# arduino_uno_to_attiny_x4.net
KiCad netlist of a schematic drawn in EAGLE
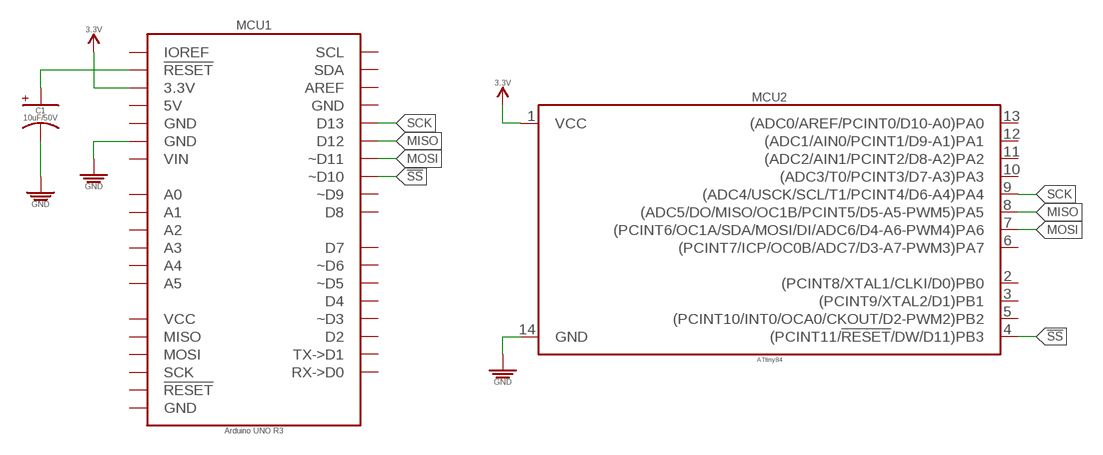
[diagram p0: schematic, sheet 1]

(export (version "E")
  (design (tool "Eeschema 10.0.6"))
  (components
    (comp (ref "C1")
      (value "10uF/50V")
      (footprint "eagle-import:_AE_PTH-DIA5-LS2-H5")
      (fields (field (name "MFR") "Panasonic Electronic Components") (field (name "MPN") "ECE-A1HKA100"))
      (libsource (lib "eagle-import") (part "10UF-POLARIZED_PTH_50V-20%"))
    )
    (comp (ref "MCU1")
      (value "Arduino UNO R3")
      (footprint "eagle-import:ARDUINO_UNO_R3")
      (fields (field (name "MFR") "Arduino") (field (name "MPN") "A000066"))
      (libsource (lib "eagle-import") (part "ARDUINO_UNO_R3"))
    )
    (comp (ref "MCU2")
      (value "ATtiny84")
      (footprint "eagle-import:DIP793W45P254L1919H533Q14B_DIP-14_ATTINY-X4")
      (fields (field (name "MFR") "Microchip Technology") (field (name "MPN") "ATTINY84A-PU"))
      (libsource (lib "eagle-import") (part "ATTINY-X4_DIP-14_ATTINY-84"))
    )
  )
  (nets
    (net (code "1") (name "/~{SS}") (class "Default")
      (node (ref "MCU1") (pin "D10") (pinfunction "~{D10}_D10") (pintype "bidirectional"))
      (node (ref "MCU2") (pin "4") (pinfunction "(PCINT11/~{RESET}/DW/D11)PB3_4") (pintype "bidirectional"))
    )
    (net (code "2") (name "3.3V") (class "Default")
      (node (ref "MCU1") (pin "3.3V") (pinfunction "3.3V_3.3V") (pintype "bidirectional"))
      (node (ref "MCU2") (pin "1") (pinfunction "VCC_1") (pintype "passive"))
    )
    (net (code "3") (name "GND") (class "Default")
      (node (ref "C1") (pin "-") (pinfunction "K_-") (pintype "passive"))
      (node (ref "MCU1") (pin "GND@3") (pinfunction "GND_GND@3") (pintype "bidirectional"))
      (node (ref "MCU2") (pin "14") (pinfunction "GND_14") (pintype "passive"))
    )
    (net (code "4") (name "MISO") (class "Default")
      (node (ref "MCU1") (pin "D12") (pinfunction "D12_D12") (pintype "bidirectional"))
      (node (ref "MCU2") (pin "8") (pinfunction "(ADC5/DO/MISO/OC1B/PCINT5/D5-A5-PWM5)PA5_8") (pintype "bidirectional"))
    )
    (net (code "5") (name "MOSI") (class "Default")
      (node (ref "MCU1") (pin "D11") (pinfunction "~{D11}_D11") (pintype "bidirectional"))
      (node (ref "MCU2") (pin "7") (pinfunction "(PCINT6/OC1A/SDA/MOSI/DI/ADC6/D4-A6-PWM4)PA6_7") (pintype "bidirectional"))
    )
    (net (code "6") (name "Net-(C1-A)") (class "Default")
      (node (ref "C1") (pin "+") (pinfunction "A_+") (pintype "passive"))
      (node (ref "MCU1") (pin "RESET@1") (pinfunction "~{RESET}_RESET@1") (pintype "bidirectional"))
    )
    (net (code "7") (name "SCK") (class "Default")
      (node (ref "MCU1") (pin "D13") (pinfunction "D13_D13") (pintype "bidirectional"))
      (node (ref "MCU2") (pin "9") (pinfunction "(ADC4/USCK/SCL/T1/PCINT4/D6-A4)PA4_9") (pintype "bidirectional"))
    )
    (net (code "8") (name "unconnected-(MCU1-GND-PadGND@1)") (class "Default")
      (node (ref "MCU1") (pin "GND@1") (pinfunction "GND_GND@1") (pintype "bidirectional"))
    )
    (net (code "9") (name "unconnected-(MCU1-GND-PadGND@2)") (class "Default")
      (node (ref "MCU1") (pin "GND@2") (pinfunction "GND_GND@2") (pintype "bidirectional"))
    )
    (net (code "10") (name "unconnected-(MCU1-GND-PadGND@4)") (class "Default")
      (node (ref "MCU1") (pin "GND@4") (pinfunction "GND_GND@4") (pintype "bidirectional"))
    )
    (net (code "11") (name "unconnected-(MCU1-Pad5V)") (class "Default")
      (node (ref "MCU1") (pin "5V") (pinfunction "5V_5V") (pintype "bidirectional"))
    )
    (net (code "12") (name "unconnected-(MCU1-PadA0)") (class "Default")
      (node (ref "MCU1") (pin "A0") (pinfunction "A0_A0") (pintype "bidirectional"))
    )
    (net (code "13") (name "unconnected-(MCU1-PadA1)") (class "Default")
      (node (ref "MCU1") (pin "A1") (pinfunction "A1_A1") (pintype "bidirectional"))
    )
    (net (code "14") (name "unconnected-(MCU1-PadA2)") (class "Default")
      (node (ref "MCU1") (pin "A2") (pinfunction "A2_A2") (pintype "bidirectional"))
    )
    (net (code "15") (name "unconnected-(MCU1-PadA3)") (class "Default")
      (node (ref "MCU1") (pin "A3") (pinfunction "A3_A3") (pintype "bidirectional"))
    )
    (net (code "16") (name "unconnected-(MCU1-PadA4)") (class "Default")
      (node (ref "MCU1") (pin "A4") (pinfunction "A4_A4") (pintype "bidirectional"))
    )
    (net (code "17") (name "unconnected-(MCU1-PadA5)") (class "Default")
      (node (ref "MCU1") (pin "A5") (pinfunction "A5_A5") (pintype "bidirectional"))
    )
    (net (code "18") (name "unconnected-(MCU1-PadAREF)") (class "Default")
      (node (ref "MCU1") (pin "AREF") (pinfunction "AREF_AREF") (pintype "bidirectional"))
    )
    (net (code "19") (name "unconnected-(MCU1-PadD2)") (class "Default")
      (node (ref "MCU1") (pin "D2") (pinfunction "D2_D2") (pintype "bidirectional"))
    )
    (net (code "20") (name "unconnected-(MCU1-PadD4)") (class "Default")
      (node (ref "MCU1") (pin "D4") (pinfunction "D4_D4") (pintype "bidirectional"))
    )
    (net (code "21") (name "unconnected-(MCU1-PadD7)") (class "Default")
      (node (ref "MCU1") (pin "D7") (pinfunction "D7_D7") (pintype "bidirectional"))
    )
    (net (code "22") (name "unconnected-(MCU1-PadD8)") (class "Default")
      (node (ref "MCU1") (pin "D8") (pinfunction "D8_D8") (pintype "bidirectional"))
    )
    (net (code "23") (name "unconnected-(MCU1-PadIOREF)") (class "Default")
      (node (ref "MCU1") (pin "IOREF") (pinfunction "IOREF_IOREF") (pintype "bidirectional"))
    )
    (net (code "24") (name "unconnected-(MCU1-PadMISO)") (class "Default")
      (node (ref "MCU1") (pin "MISO") (pinfunction "MISO_MISO") (pintype "bidirectional"))
    )
    (net (code "25") (name "unconnected-(MCU1-PadMOSI)") (class "Default")
      (node (ref "MCU1") (pin "MOSI") (pinfunction "MOSI_MOSI") (pintype "bidirectional"))
    )
    (net (code "26") (name "unconnected-(MCU1-PadSCK)") (class "Default")
      (node (ref "MCU1") (pin "SCK") (pinfunction "SCK_SCK") (pintype "bidirectional"))
    )
    (net (code "27") (name "unconnected-(MCU1-PadSCL)") (class "Default")
      (node (ref "MCU1") (pin "SCL") (pinfunction "SCL_SCL") (pintype "bidirectional"))
    )
    (net (code "28") (name "unconnected-(MCU1-PadSDA)") (class "Default")
      (node (ref "MCU1") (pin "SDA") (pinfunction "SDA_SDA") (pintype "bidirectional"))
    )
    (net (code "29") (name "unconnected-(MCU1-PadVCC)") (class "Default")
      (node (ref "MCU1") (pin "VCC") (pinfunction "VCC_VCC") (pintype "bidirectional"))
    )
    (net (code "30") (name "unconnected-(MCU1-PadVIN)") (class "Default")
      (node (ref "MCU1") (pin "VIN") (pinfunction "VIN_VIN") (pintype "bidirectional"))
    )
    (net (code "31") (name "unconnected-(MCU1-RX->D0-PadD0)") (class "Default")
      (node (ref "MCU1") (pin "D0") (pinfunction "RX->D0_D0") (pintype "bidirectional"))
    )
    (net (code "32") (name "unconnected-(MCU1-TX->D1-PadD1)") (class "Default")
      (node (ref "MCU1") (pin "D1") (pinfunction "TX->D1_D1") (pintype "bidirectional"))
    )
    (net (code "33") (name "unconnected-(MCU1-~{D3}-PadD3)") (class "Default")
      (node (ref "MCU1") (pin "D3") (pinfunction "~{D3}_D3") (pintype "bidirectional"))
    )
    (net (code "34") (name "unconnected-(MCU1-~{D5}-PadD5)") (class "Default")
      (node (ref "MCU1") (pin "D5") (pinfunction "~{D5}_D5") (pintype "bidirectional"))
    )
    (net (code "35") (name "unconnected-(MCU1-~{D6}-PadD6)") (class "Default")
      (node (ref "MCU1") (pin "D6") (pinfunction "~{D6}_D6") (pintype "bidirectional"))
    )
    (net (code "36") (name "unconnected-(MCU1-~{D9}-PadD9)") (class "Default")
      (node (ref "MCU1") (pin "D9") (pinfunction "~{D9}_D9") (pintype "bidirectional"))
    )
    (net (code "37") (name "unconnected-(MCU1-~{RESET}-PadRESET@2)") (class "Default")
      (node (ref "MCU1") (pin "RESET@2") (pinfunction "~{RESET}_RESET@2") (pintype "bidirectional"))
    )
    (net (code "38") (name "unconnected-(MCU2-(ADC0{slash}AREF{slash}PCINT0{slash}D10-A0)PA0-Pad13)") (class "Default")
      (node (ref "MCU2") (pin "13") (pinfunction "(ADC0/AREF/PCINT0/D10-A0)PA0_13") (pintype "bidirectional"))
    )
    (net (code "39") (name "unconnected-(MCU2-(ADC1{slash}AIN0{slash}PCINT1{slash}D9-A1)PA1-Pad12)") (class "Default")
      (node (ref "MCU2") (pin "12") (pinfunction "(ADC1/AIN0/PCINT1/D9-A1)PA1_12") (pintype "bidirectional"))
    )
    (net (code "40") (name "unconnected-(MCU2-(ADC2{slash}AIN1{slash}PCINT2{slash}D8-A2)PA2-Pad11)") (class "Default")
      (node (ref "MCU2") (pin "11") (pinfunction "(ADC2/AIN1/PCINT2/D8-A2)PA2_11") (pintype "bidirectional"))
    )
    (net (code "41") (name "unconnected-(MCU2-(ADC3{slash}T0{slash}PCINT3{slash}D7-A3)PA3-Pad10)") (class "Default")
      (node (ref "MCU2") (pin "10") (pinfunction "(ADC3/T0/PCINT3/D7-A3)PA3_10") (pintype "bidirectional"))
    )
    (net (code "42") (name "unconnected-(MCU2-(PCINT7{slash}ICP{slash}OC0B{slash}ADC7{slash}D3-A7-PWM3)PA7-Pad6)") (class "Default")
      (node (ref "MCU2") (pin "6") (pinfunction "(PCINT7/ICP/OC0B/ADC7/D3-A7-PWM3)PA7_6") (pintype "bidirectional"))
    )
    (net (code "43") (name "unconnected-(MCU2-(PCINT8{slash}XTAL1{slash}CLKI{slash}D0)PB0-Pad2)") (class "Default")
      (node (ref "MCU2") (pin "2") (pinfunction "(PCINT8/XTAL1/CLKI/D0)PB0_2") (pintype "bidirectional"))
    )
    (net (code "44") (name "unconnected-(MCU2-(PCINT9{slash}XTAL2{slash}D1)PB1-Pad3)") (class "Default")
      (node (ref "MCU2") (pin "3") (pinfunction "(PCINT9/XTAL2/D1)PB1_3") (pintype "bidirectional"))
    )
    (net (code "45") (name "unconnected-(MCU2-(PCINT10{slash}INT0{slash}OCA0{slash}CKOUT{slash}D2-PWM2)PB2-Pad5)") (class "Default")
      (node (ref "MCU2") (pin "5") (pinfunction "(PCINT10/INT0/OCA0/CKOUT/D2-PWM2)PB2_5") (pintype "bidirectional"))
    )
  )
)
